# eurorack-passive-switches.net
KiCad netlist of a schematic drawn in EAGLE
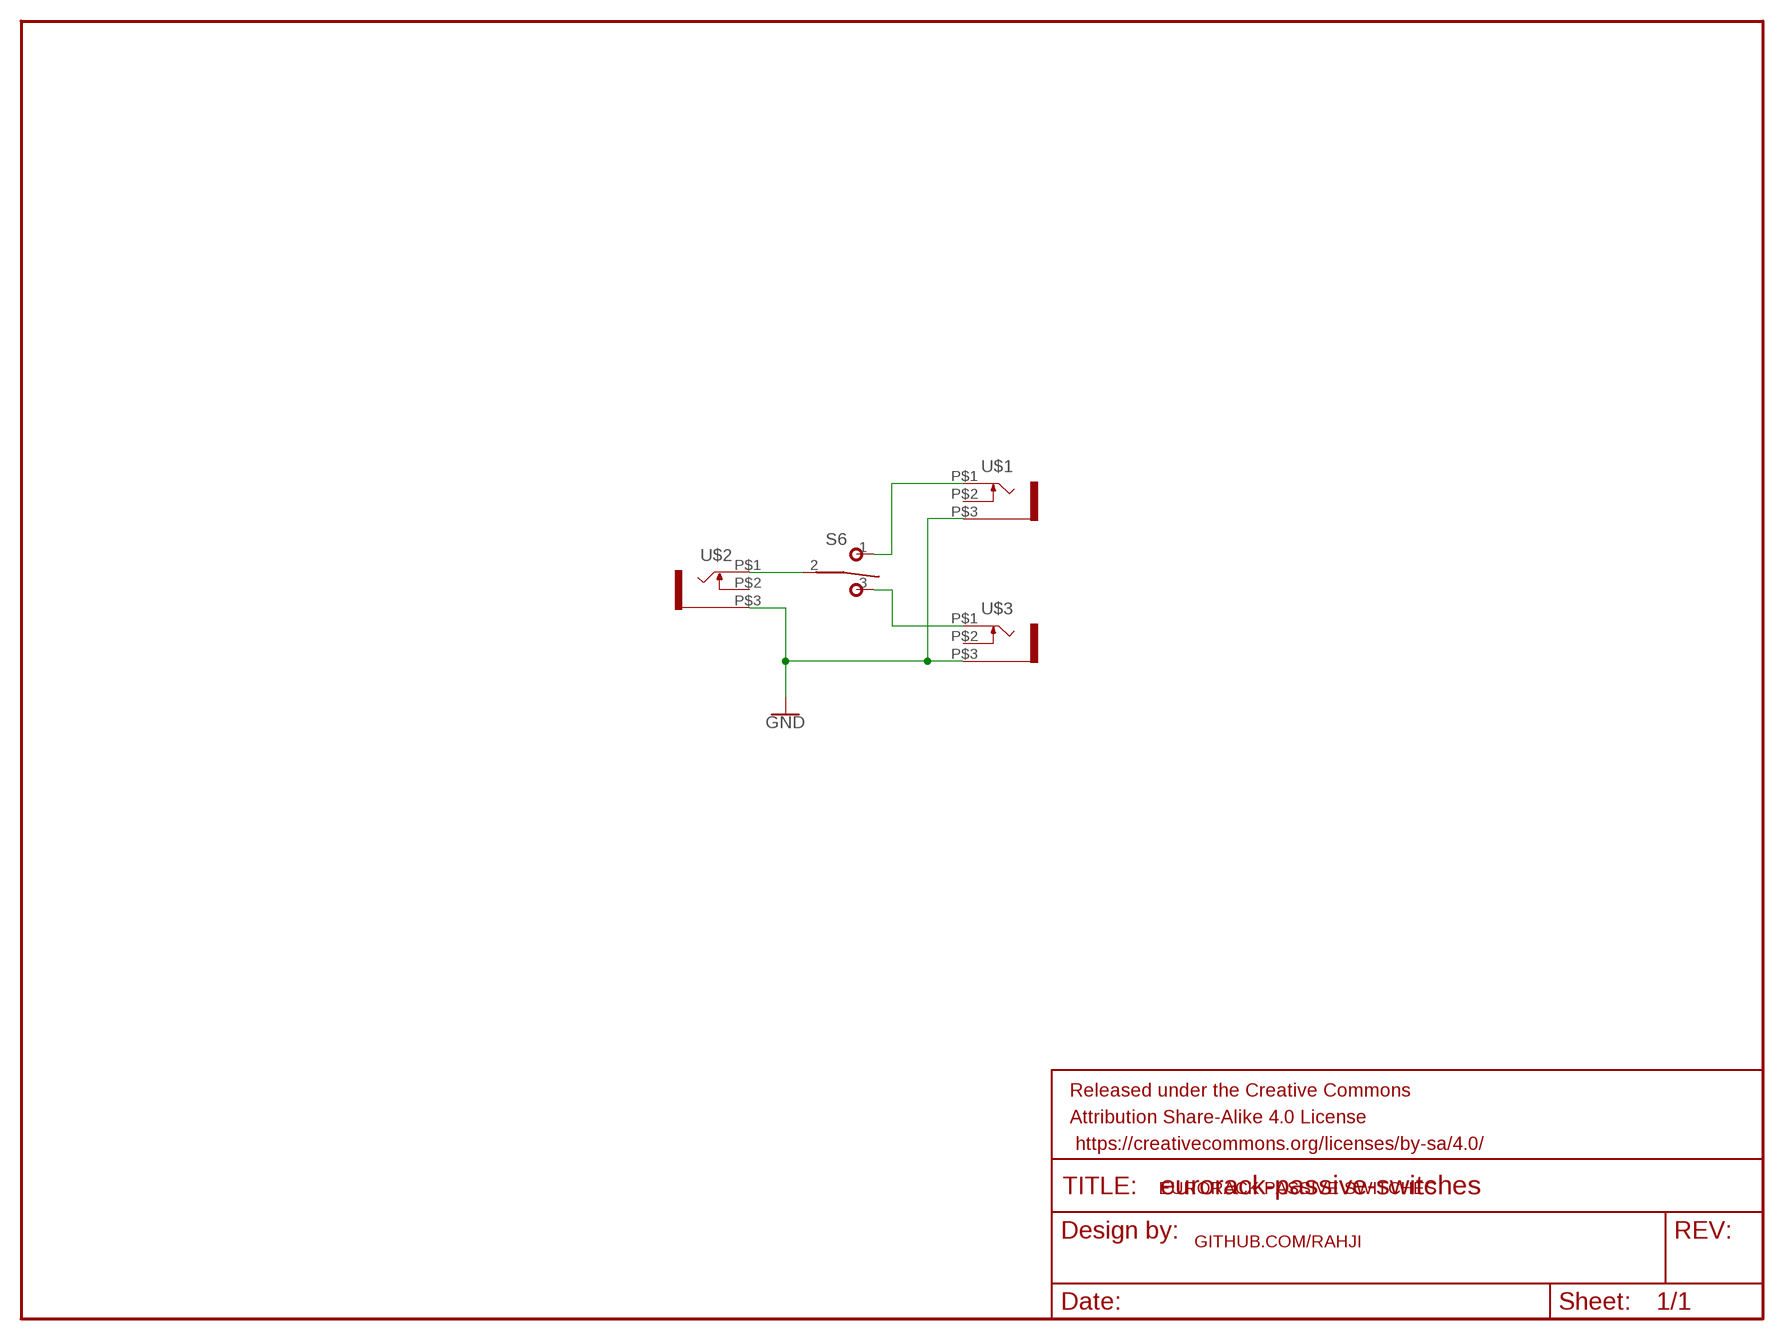
[diagram p0: schematic, sheet 1]

(export (version "E")
  (design (tool "Eeschema 10.0.6"))
  (components
    (comp (ref "FRAME1")
      (value "FRAME-LETTERNO_PACKAGE")
      (footprint "eagle-import:DUMMY")
      (fields (field (name "DESIGNER") "Nobody"))
      (libsource (lib "eagle-import") (part "FRAME-LETTERNO_PACKAGE"))
    )
    (comp (ref "S6")
      (value "SPDT")
      (footprint "eagle-import:M9040P")
      (libsource (lib "eagle-import") (part "SPDT"))
    )
    (comp (ref "U$1")
      (value "OUT")
      (footprint "eagle-import:WQP-PJ301M-12_JACK")
      (libsource (lib "eagle-import") (part "WQP-PJ301M-12_JACK"))
    )
    (comp (ref "U$2")
      (value "IN")
      (footprint "eagle-import:WQP-PJ301M-12_JACK")
      (libsource (lib "eagle-import") (part "WQP-PJ301M-12_JACK"))
    )
    (comp (ref "U$3")
      (value "OUT")
      (footprint "eagle-import:WQP-PJ301M-12_JACK")
      (libsource (lib "eagle-import") (part "WQP-PJ301M-12_JACK"))
    )
  )
  (nets
    (net (code "1") (name "GND") (class "Default")
      (node (ref "U$1") (pin "P$3") (pinfunction "1_P$3") (pintype "passive"))
      (node (ref "U$2") (pin "P$3") (pinfunction "1_P$3") (pintype "passive"))
      (node (ref "U$3") (pin "P$3") (pinfunction "1_P$3") (pintype "passive"))
    )
    (net (code "2") (name "Net-(S6-O)") (class "Default")
      (node (ref "S6") (pin "1") (pinfunction "O_1") (pintype "passive"))
      (node (ref "U$1") (pin "P$1") (pinfunction "2_P$1") (pintype "passive"))
    )
    (net (code "3") (name "Net-(S6-P)") (class "Default")
      (node (ref "S6") (pin "2") (pinfunction "P_2") (pintype "passive"))
      (node (ref "U$2") (pin "P$1") (pinfunction "2_P$1") (pintype "passive"))
    )
    (net (code "4") (name "Net-(S6-S)") (class "Default")
      (node (ref "S6") (pin "3") (pinfunction "S_3") (pintype "passive"))
      (node (ref "U$3") (pin "P$1") (pinfunction "2_P$1") (pintype "passive"))
    )
    (net (code "5") (name "unconnected-(U$1-3-PadP$2)") (class "Default")
      (node (ref "U$1") (pin "P$2") (pinfunction "3_P$2") (pintype "passive"))
    )
    (net (code "6") (name "unconnected-(U$2-3-PadP$2)") (class "Default")
      (node (ref "U$2") (pin "P$2") (pinfunction "3_P$2") (pintype "passive"))
    )
    (net (code "7") (name "unconnected-(U$3-3-PadP$2)") (class "Default")
      (node (ref "U$3") (pin "P$2") (pinfunction "3_P$2") (pintype "passive"))
    )
  )
)
